# sn76489-simple-sound.net
KiCad netlist of a schematic drawn in EAGLE
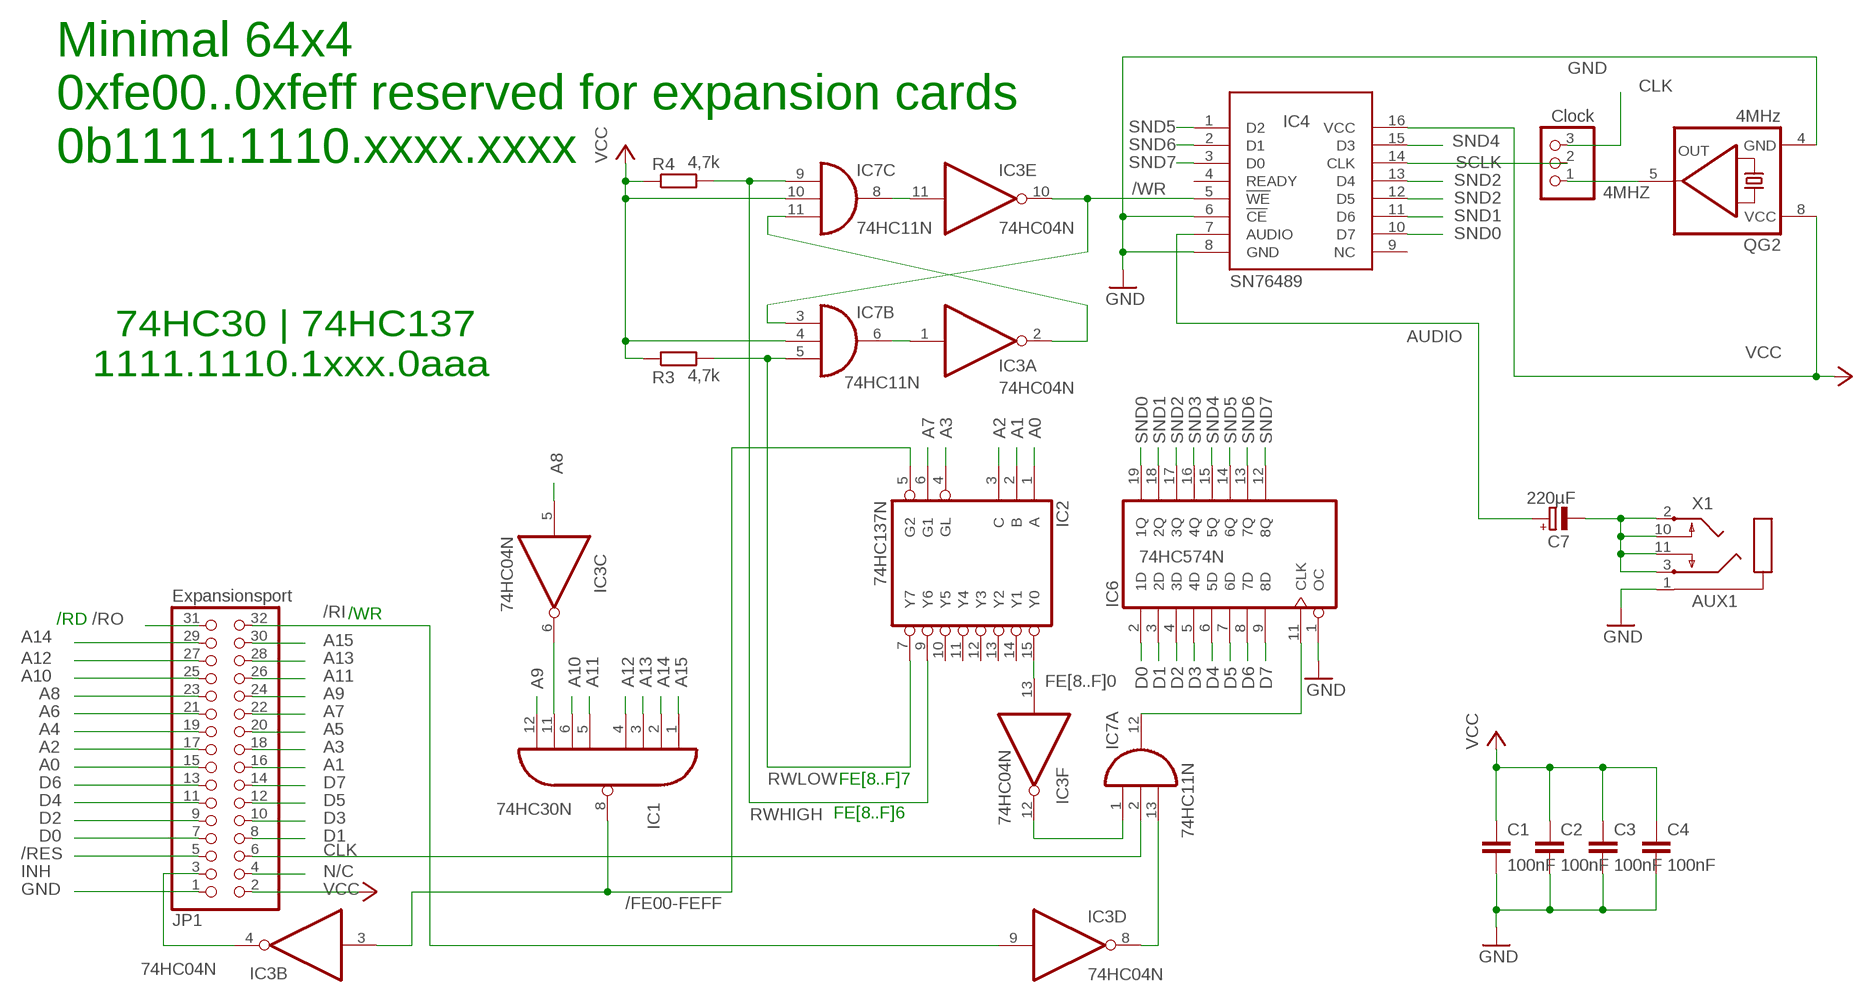
[diagram p0: schematic, sheet 1]

(export (version "E")
  (design (tool "Eeschema 10.0.6"))
  (components
    (comp (ref "C1")
      (value "100nF")
      (footprint "eagle-import:C050-025X075")
      (libsource (lib "eagle-import") (part "C-EU050-025X075"))
    )
    (comp (ref "C2")
      (value "100nF")
      (footprint "eagle-import:C050-025X075")
      (libsource (lib "eagle-import") (part "C-EU050-025X075"))
    )
    (comp (ref "C3")
      (value "100nF")
      (footprint "eagle-import:C050-025X075")
      (libsource (lib "eagle-import") (part "C-EU050-025X075"))
    )
    (comp (ref "C4")
      (value "100nF")
      (footprint "eagle-import:C050-025X075")
      (libsource (lib "eagle-import") (part "C-EU050-025X075"))
    )
    (comp (ref "C7")
      (value "220µF")
      (footprint "eagle-import:E2,5-7")
      (libsource (lib "eagle-import") (part "CPOL-EUE2.5-7"))
    )
    (comp (ref "IC1")
      (value "74HC30N")
      (footprint "eagle-import:DIL14")
      (libsource (lib "eagle-import") (part "7430NHC"))
    )
    (comp (ref "IC2")
      (value "74HC137N")
      (footprint "eagle-import:DIL16")
      (libsource (lib "eagle-import") (part "74137NHC"))
    )
    (comp (ref "IC3")
      (value "74HC04N")
      (footprint "eagle-import:DIL14")
      (libsource (lib "eagle-import") (part "7404NHC"))
    )
    (comp (ref "IC4")
      (value "SN76489")
      (footprint "eagle-import:ALEX-PARTS_DIL16")
      (libsource (lib "eagle-import") (part "ALEX-PARTS_SN76489AN"))
    )
    (comp (ref "IC6")
      (value "74HC574N")
      (footprint "eagle-import:DIL20")
      (libsource (lib "eagle-import") (part "74574NHC"))
    )
    (comp (ref "IC7")
      (value "74HC11N")
      (footprint "eagle-import:DIL14")
      (libsource (lib "eagle-import") (part "7411NHC"))
    )
    (comp (ref "JP1")
      (value "Expansionsport")
      (footprint "eagle-import:2X16")
      (libsource (lib "eagle-import") (part "PINHD-2X16"))
    )
    (comp (ref "JP6")
      (value "Clock")
      (footprint "eagle-import:1X03")
      (libsource (lib "eagle-import") (part "PINHD-1X3"))
    )
    (comp (ref "QG2")
      (value "4MHz")
      (footprint "eagle-import:DIL08S")
      (libsource (lib "eagle-import") (part "QG5460"))
    )
    (comp (ref "R3")
      (value "4,7k")
      (footprint "eagle-import:0207_10")
      (libsource (lib "eagle-import") (part "R-EU_0207/10"))
    )
    (comp (ref "R4")
      (value "4,7k")
      (footprint "eagle-import:0207_10")
      (libsource (lib "eagle-import") (part "R-EU_0207/10"))
    )
    (comp (ref "X1")
      (value "AUX1")
      (footprint "eagle-import:SJ1-352XN")
      (libsource (lib "eagle-import") (part "CON-SJ1-352XNSJ1-352XN"))
    )
  )
  (nets
    (net (code "1") (name "/4MHZ") (class "Default")
      (node (ref "JP6") (pin "1") (pinfunction "1_1") (pintype "passive"))
      (node (ref "QG2") (pin "5") (pinfunction "OUT_5") (pintype "output"))
    )
    (net (code "2") (name "/A0") (class "Default")
      (node (ref "IC2") (pin "1") (pinfunction "A_1") (pintype "input"))
      (node (ref "JP1") (pin "15") (pinfunction "15_15") (pintype "passive"))
    )
    (net (code "3") (name "/A1") (class "Default")
      (node (ref "IC2") (pin "2") (pinfunction "B_2") (pintype "input"))
      (node (ref "JP1") (pin "16") (pinfunction "16_16") (pintype "passive"))
    )
    (net (code "4") (name "/A2") (class "Default")
      (node (ref "IC2") (pin "3") (pinfunction "C_3") (pintype "input"))
      (node (ref "JP1") (pin "17") (pinfunction "17_17") (pintype "passive"))
    )
    (net (code "5") (name "/A3") (class "Default")
      (node (ref "IC2") (pin "4") (pinfunction "GL_4") (pintype "input"))
      (node (ref "JP1") (pin "18") (pinfunction "18_18") (pintype "passive"))
    )
    (net (code "6") (name "/A4") (class "Default")
      (node (ref "JP1") (pin "19") (pinfunction "19_19") (pintype "passive"))
    )
    (net (code "7") (name "/A5") (class "Default")
      (node (ref "JP1") (pin "20") (pinfunction "20_20") (pintype "passive"))
    )
    (net (code "8") (name "/A6") (class "Default")
      (node (ref "JP1") (pin "21") (pinfunction "21_21") (pintype "passive"))
    )
    (net (code "9") (name "/A7") (class "Default")
      (node (ref "IC2") (pin "6") (pinfunction "G1_6") (pintype "input"))
      (node (ref "JP1") (pin "22") (pinfunction "22_22") (pintype "passive"))
    )
    (net (code "10") (name "/A8") (class "Default")
      (node (ref "IC3") (pin "5") (pinfunction "I_5") (pintype "input"))
      (node (ref "JP1") (pin "23") (pinfunction "23_23") (pintype "passive"))
    )
    (net (code "11") (name "/A9") (class "Default")
      (node (ref "IC1") (pin "12") (pinfunction "I7_12") (pintype "input"))
      (node (ref "JP1") (pin "24") (pinfunction "24_24") (pintype "passive"))
    )
    (net (code "12") (name "/A10") (class "Default")
      (node (ref "IC1") (pin "6") (pinfunction "I5_6") (pintype "input"))
      (node (ref "JP1") (pin "25") (pinfunction "25_25") (pintype "passive"))
    )
    (net (code "13") (name "/A11") (class "Default")
      (node (ref "IC1") (pin "5") (pinfunction "I4_5") (pintype "input"))
      (node (ref "JP1") (pin "26") (pinfunction "26_26") (pintype "passive"))
    )
    (net (code "14") (name "/A12") (class "Default")
      (node (ref "IC1") (pin "4") (pinfunction "I3_4") (pintype "input"))
      (node (ref "JP1") (pin "27") (pinfunction "27_27") (pintype "passive"))
    )
    (net (code "15") (name "/A13") (class "Default")
      (node (ref "IC1") (pin "3") (pinfunction "I2_3") (pintype "input"))
      (node (ref "JP1") (pin "28") (pinfunction "28_28") (pintype "passive"))
    )
    (net (code "16") (name "/A14") (class "Default")
      (node (ref "IC1") (pin "2") (pinfunction "I1_2") (pintype "input"))
      (node (ref "JP1") (pin "29") (pinfunction "29_29") (pintype "passive"))
    )
    (net (code "17") (name "/A15") (class "Default")
      (node (ref "IC1") (pin "1") (pinfunction "I0_1") (pintype "input"))
      (node (ref "JP1") (pin "30") (pinfunction "30_30") (pintype "passive"))
    )
    (net (code "18") (name "/AUDIO") (class "Default")
      (node (ref "C7") (pin "+") (pinfunction "+_+") (pintype "passive"))
      (node (ref "IC4") (pin "7") (pinfunction "AUDIO_7") (pintype "output"))
    )
    (net (code "19") (name "/CLK") (class "Default")
      (node (ref "IC7") (pin "2") (pinfunction "I1_2") (pintype "input"))
      (node (ref "JP1") (pin "6") (pinfunction "6_6") (pintype "passive"))
      (node (ref "JP6") (pin "3") (pinfunction "3_3") (pintype "passive"))
    )
    (net (code "20") (name "/D0") (class "Default")
      (node (ref "IC6") (pin "2") (pinfunction "1D_2") (pintype "input"))
      (node (ref "JP1") (pin "7") (pinfunction "7_7") (pintype "passive"))
    )
    (net (code "21") (name "/D1") (class "Default")
      (node (ref "IC6") (pin "3") (pinfunction "2D_3") (pintype "input"))
      (node (ref "JP1") (pin "8") (pinfunction "8_8") (pintype "passive"))
    )
    (net (code "22") (name "/D2") (class "Default")
      (node (ref "IC6") (pin "4") (pinfunction "3D_4") (pintype "input"))
      (node (ref "JP1") (pin "9") (pinfunction "9_9") (pintype "passive"))
    )
    (net (code "23") (name "/D3") (class "Default")
      (node (ref "IC6") (pin "5") (pinfunction "4D_5") (pintype "input"))
      (node (ref "JP1") (pin "10") (pinfunction "10_10") (pintype "passive"))
    )
    (net (code "24") (name "/D4") (class "Default")
      (node (ref "IC6") (pin "6") (pinfunction "5D_6") (pintype "input"))
      (node (ref "JP1") (pin "11") (pinfunction "11_11") (pintype "passive"))
    )
    (net (code "25") (name "/D5") (class "Default")
      (node (ref "IC6") (pin "7") (pinfunction "6D_7") (pintype "input"))
      (node (ref "JP1") (pin "12") (pinfunction "12_12") (pintype "passive"))
    )
    (net (code "26") (name "/D6") (class "Default")
      (node (ref "IC6") (pin "8") (pinfunction "7D_8") (pintype "input"))
      (node (ref "JP1") (pin "13") (pinfunction "13_13") (pintype "passive"))
    )
    (net (code "27") (name "/D7") (class "Default")
      (node (ref "IC6") (pin "9") (pinfunction "8D_9") (pintype "input"))
      (node (ref "JP1") (pin "14") (pinfunction "14_14") (pintype "passive"))
    )
    (net (code "28") (name "/FE[8..F]0") (class "Default")
      (node (ref "IC2") (pin "15") (pinfunction "Y0_15") (pintype "output"))
      (node (ref "IC3") (pin "13") (pinfunction "I_13") (pintype "input"))
    )
    (net (code "29") (name "/INH") (class "Default")
      (node (ref "IC3") (pin "4") (pinfunction "O_4") (pintype "output"))
      (node (ref "JP1") (pin "3") (pinfunction "3_3") (pintype "passive"))
    )
    (net (code "30") (name "/N{slash}C") (class "Default")
      (node (ref "JP1") (pin "4") (pinfunction "4_4") (pintype "passive"))
    )
    (net (code "31") (name "/RWHIGH") (class "Default")
      (node (ref "IC2") (pin "9") (pinfunction "Y6_9") (pintype "output"))
      (node (ref "IC7") (pin "9") (pinfunction "I0_9") (pintype "input"))
      (node (ref "R4") (pin "2") (pinfunction "2_2") (pintype "passive"))
    )
    (net (code "32") (name "/RWLOW") (class "Default")
      (node (ref "IC2") (pin "7") (pinfunction "Y7_7") (pintype "output"))
      (node (ref "IC7") (pin "5") (pinfunction "I2_5") (pintype "input"))
      (node (ref "R3") (pin "2") (pinfunction "2_2") (pintype "passive"))
    )
    (net (code "33") (name "/SCLK") (class "Default")
      (node (ref "IC4") (pin "14") (pinfunction "CLK_14") (pintype "input"))
      (node (ref "JP6") (pin "2") (pinfunction "2_2") (pintype "passive"))
    )
    (net (code "34") (name "/SND0") (class "Default")
      (node (ref "IC4") (pin "10") (pinfunction "D7_10") (pintype "input"))
      (node (ref "IC6") (pin "19") (pinfunction "1Q_19") (pintype "tri_state"))
    )
    (net (code "35") (name "/SND1") (class "Default")
      (node (ref "IC4") (pin "11") (pinfunction "D6_11") (pintype "input"))
      (node (ref "IC6") (pin "18") (pinfunction "2Q_18") (pintype "tri_state"))
    )
    (net (code "36") (name "/SND2") (class "Default")
      (node (ref "IC4") (pin "12") (pinfunction "D5_12") (pintype "input"))
      (node (ref "IC4") (pin "13") (pinfunction "D4_13") (pintype "input"))
      (node (ref "IC6") (pin "17") (pinfunction "3Q_17") (pintype "tri_state"))
    )
    (net (code "37") (name "/SND3") (class "Default")
      (node (ref "IC6") (pin "16") (pinfunction "4Q_16") (pintype "tri_state"))
    )
    (net (code "38") (name "/SND4") (class "Default")
      (node (ref "IC4") (pin "15") (pinfunction "D3_15") (pintype "input"))
      (node (ref "IC6") (pin "15") (pinfunction "5Q_15") (pintype "tri_state"))
    )
    (net (code "39") (name "/SND5") (class "Default")
      (node (ref "IC4") (pin "1") (pinfunction "D2_1") (pintype "input"))
      (node (ref "IC6") (pin "14") (pinfunction "6Q_14") (pintype "tri_state"))
    )
    (net (code "40") (name "/SND6") (class "Default")
      (node (ref "IC4") (pin "2") (pinfunction "D1_2") (pintype "input"))
      (node (ref "IC6") (pin "13") (pinfunction "7Q_13") (pintype "tri_state"))
    )
    (net (code "41") (name "/SND7") (class "Default")
      (node (ref "IC4") (pin "3") (pinfunction "D0_3") (pintype "input"))
      (node (ref "IC6") (pin "12") (pinfunction "8Q_12") (pintype "tri_state"))
    )
    (net (code "42") (name "/{slash}FE00-FEFF") (class "Default")
      (node (ref "IC1") (pin "8") (pinfunction "O_8") (pintype "output"))
      (node (ref "IC2") (pin "5") (pinfunction "G2_5") (pintype "input"))
      (node (ref "IC3") (pin "3") (pinfunction "I_3") (pintype "input"))
    )
    (net (code "43") (name "/{slash}RES") (class "Default")
      (node (ref "JP1") (pin "5") (pinfunction "5_5") (pintype "passive"))
    )
    (net (code "44") (name "/{slash}RI") (class "Default")
      (node (ref "IC3") (pin "9") (pinfunction "I_9") (pintype "input"))
      (node (ref "JP1") (pin "32") (pinfunction "32_32") (pintype "passive"))
    )
    (net (code "45") (name "/{slash}RO") (class "Default")
      (node (ref "JP1") (pin "31") (pinfunction "31_31") (pintype "passive"))
    )
    (net (code "46") (name "/{slash}WR") (class "Default")
      (node (ref "IC3") (pin "10") (pinfunction "O_10") (pintype "output"))
      (node (ref "IC4") (pin "5") (pinfunction "~{WE}_5") (pintype "input"))
      (node (ref "IC7") (pin "3") (pinfunction "I0_3") (pintype "input"))
    )
    (net (code "47") (name "GND") (class "Default")
      (node (ref "C1") (pin "2") (pinfunction "2_2") (pintype "passive"))
      (node (ref "C2") (pin "2") (pinfunction "2_2") (pintype "passive"))
      (node (ref "C3") (pin "2") (pinfunction "2_2") (pintype "passive"))
      (node (ref "C4") (pin "2") (pinfunction "2_2") (pintype "passive"))
      (node (ref "IC4") (pin "6") (pinfunction "~{CE}_6") (pintype "input"))
      (node (ref "IC4") (pin "8") (pinfunction "GND_8") (pintype "power_in"))
      (node (ref "IC6") (pin "1") (pinfunction "OC_1") (pintype "input"))
      (node (ref "JP1") (pin "1") (pinfunction "1_1") (pintype "passive"))
      (node (ref "QG2") (pin "4") (pinfunction "GND_4") (pintype "power_in"))
      (node (ref "X1") (pin "1") (pinfunction "1_1") (pintype "passive"))
    )
    (net (code "48") (name "Net-(C7-Pad-)") (class "Default")
      (node (ref "C7") (pin "-") (pinfunction "-_-") (pintype "passive"))
      (node (ref "X1") (pin "10") (pinfunction "10_10") (pintype "passive"))
      (node (ref "X1") (pin "11") (pinfunction "11_11") (pintype "passive"))
      (node (ref "X1") (pin "2") (pinfunction "2_2") (pintype "passive"))
      (node (ref "X1") (pin "3") (pinfunction "3_3") (pintype "passive"))
    )
    (net (code "49") (name "Net-(IC1A-I6)") (class "Default")
      (node (ref "IC1") (pin "11") (pinfunction "I6_11") (pintype "input"))
      (node (ref "IC3") (pin "6") (pinfunction "O_6") (pintype "output"))
    )
    (net (code "50") (name "Net-(IC3A-I)") (class "Default")
      (node (ref "IC3") (pin "1") (pinfunction "I_1") (pintype "input"))
      (node (ref "IC7") (pin "6") (pinfunction "O_6") (pintype "output"))
    )
    (net (code "51") (name "Net-(IC3A-O)") (class "Default")
      (node (ref "IC3") (pin "2") (pinfunction "O_2") (pintype "output"))
      (node (ref "IC7") (pin "11") (pinfunction "I2_11") (pintype "input"))
    )
    (net (code "52") (name "Net-(IC3D-O)") (class "Default")
      (node (ref "IC3") (pin "8") (pinfunction "O_8") (pintype "output"))
      (node (ref "IC7") (pin "13") (pinfunction "I2_13") (pintype "input"))
    )
    (net (code "53") (name "Net-(IC3E-I)") (class "Default")
      (node (ref "IC3") (pin "11") (pinfunction "I_11") (pintype "input"))
      (node (ref "IC7") (pin "8") (pinfunction "O_8") (pintype "output"))
    )
    (net (code "54") (name "Net-(IC3F-O)") (class "Default")
      (node (ref "IC3") (pin "12") (pinfunction "O_12") (pintype "output"))
      (node (ref "IC7") (pin "1") (pinfunction "I0_1") (pintype "input"))
    )
    (net (code "55") (name "Net-(IC6A-CLK)") (class "Default")
      (node (ref "IC6") (pin "11") (pinfunction "CLK_11") (pintype "input"))
      (node (ref "IC7") (pin "12") (pinfunction "O_12") (pintype "output"))
    )
    (net (code "56") (name "VCC") (class "Default")
      (node (ref "C1") (pin "1") (pinfunction "1_1") (pintype "passive"))
      (node (ref "C2") (pin "1") (pinfunction "1_1") (pintype "passive"))
      (node (ref "C3") (pin "1") (pinfunction "1_1") (pintype "passive"))
      (node (ref "C4") (pin "1") (pinfunction "1_1") (pintype "passive"))
      (node (ref "IC4") (pin "16") (pinfunction "VCC_16") (pintype "input"))
      (node (ref "IC7") (pin "10") (pinfunction "I1_10") (pintype "input"))
      (node (ref "IC7") (pin "4") (pinfunction "I1_4") (pintype "input"))
      (node (ref "JP1") (pin "2") (pinfunction "2_2") (pintype "passive"))
      (node (ref "QG2") (pin "8") (pinfunction "VCC_8") (pintype "power_in"))
      (node (ref "R3") (pin "1") (pinfunction "1_1") (pintype "passive"))
      (node (ref "R4") (pin "1") (pinfunction "1_1") (pintype "passive"))
    )
    (net (code "57") (name "unconnected-(IC2A-Y1-Pad14)") (class "Default")
      (node (ref "IC2") (pin "14") (pinfunction "Y1_14") (pintype "output"))
    )
    (net (code "58") (name "unconnected-(IC2A-Y2-Pad13)") (class "Default")
      (node (ref "IC2") (pin "13") (pinfunction "Y2_13") (pintype "output"))
    )
    (net (code "59") (name "unconnected-(IC2A-Y3-Pad12)") (class "Default")
      (node (ref "IC2") (pin "12") (pinfunction "Y3_12") (pintype "output"))
    )
    (net (code "60") (name "unconnected-(IC2A-Y4-Pad11)") (class "Default")
      (node (ref "IC2") (pin "11") (pinfunction "Y4_11") (pintype "output"))
    )
    (net (code "61") (name "unconnected-(IC2A-Y5-Pad10)") (class "Default")
      (node (ref "IC2") (pin "10") (pinfunction "Y5_10") (pintype "output"))
    )
    (net (code "62") (name "unconnected-(IC4-NC-Pad9)") (class "Default")
      (node (ref "IC4") (pin "9") (pinfunction "NC_9") (pintype "no_connect"))
    )
    (net (code "63") (name "unconnected-(IC4-READY-Pad4)") (class "Default")
      (node (ref "IC4") (pin "4") (pinfunction "READY_4") (pintype "output"))
    )
  )
)
